# untitled.net
KiCad netlist of a schematic drawn in EAGLE
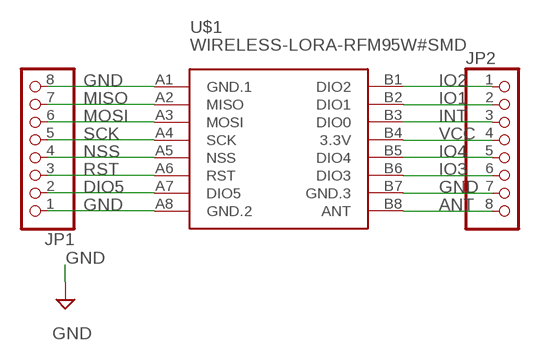
[diagram p0: schematic, sheet 1]

(export (version "E")
  (design (tool "Eeschema 10.0.6"))
  (components
    (comp (ref "JP1")
      (value "PINHD-1X8")
      (footprint "eagle-import:1X08")
      (libsource (lib "eagle-import") (part "PINHD-1X8"))
    )
    (comp (ref "JP2")
      (value "PINHD-1X8")
      (footprint "eagle-import:1X08")
      (libsource (lib "eagle-import") (part "PINHD-1X8"))
    )
    (comp (ref "U$1")
      (value "WIRELESS-LORA-RFM95W#SMD")
      (footprint "eagle-import:WIRELESS-LORA-RFM95W#SMD")
      (libsource (lib "eagle-import") (part "WIRELESS-LORA-RFM95W#SMD"))
    )
  )
  (nets
    (net (code "1") (name "/ANT") (class "Default")
      (node (ref "JP2") (pin "8") (pinfunction "8_8") (pintype "passive"))
      (node (ref "U$1") (pin "B8") (pinfunction "ANT_B8") (pintype "passive"))
    )
    (net (code "2") (name "/DIO5") (class "Default")
      (node (ref "JP1") (pin "2") (pinfunction "2_2") (pintype "passive"))
      (node (ref "U$1") (pin "A7") (pinfunction "DIO5_A7") (pintype "bidirectional"))
    )
    (net (code "3") (name "/INT") (class "Default")
      (node (ref "JP2") (pin "3") (pinfunction "3_3") (pintype "passive"))
      (node (ref "U$1") (pin "B3") (pinfunction "DIO0_B3") (pintype "bidirectional"))
    )
    (net (code "4") (name "/IO1") (class "Default")
      (node (ref "JP2") (pin "2") (pinfunction "2_2") (pintype "passive"))
      (node (ref "U$1") (pin "B2") (pinfunction "DIO1_B2") (pintype "bidirectional"))
    )
    (net (code "5") (name "/IO2") (class "Default")
      (node (ref "JP2") (pin "1") (pinfunction "1_1") (pintype "passive"))
      (node (ref "U$1") (pin "B1") (pinfunction "DIO2_B1") (pintype "bidirectional"))
    )
    (net (code "6") (name "/IO3") (class "Default")
      (node (ref "JP2") (pin "6") (pinfunction "6_6") (pintype "passive"))
      (node (ref "U$1") (pin "B6") (pinfunction "DIO3_B6") (pintype "bidirectional"))
    )
    (net (code "7") (name "/IO4") (class "Default")
      (node (ref "JP2") (pin "5") (pinfunction "5_5") (pintype "passive"))
      (node (ref "U$1") (pin "B5") (pinfunction "DIO4_B5") (pintype "bidirectional"))
    )
    (net (code "8") (name "/MISO") (class "Default")
      (node (ref "JP1") (pin "7") (pinfunction "7_7") (pintype "passive"))
      (node (ref "U$1") (pin "A2") (pinfunction "MISO_A2") (pintype "bidirectional"))
    )
    (net (code "9") (name "/MOSI") (class "Default")
      (node (ref "JP1") (pin "6") (pinfunction "6_6") (pintype "passive"))
      (node (ref "U$1") (pin "A3") (pinfunction "MOSI_A3") (pintype "bidirectional"))
    )
    (net (code "10") (name "/NSS") (class "Default")
      (node (ref "JP1") (pin "4") (pinfunction "4_4") (pintype "passive"))
      (node (ref "U$1") (pin "A5") (pinfunction "NSS_A5") (pintype "bidirectional"))
    )
    (net (code "11") (name "/RST") (class "Default")
      (node (ref "JP1") (pin "3") (pinfunction "3_3") (pintype "passive"))
      (node (ref "U$1") (pin "A6") (pinfunction "RST_A6") (pintype "bidirectional"))
    )
    (net (code "12") (name "/SCK") (class "Default")
      (node (ref "JP1") (pin "5") (pinfunction "5_5") (pintype "passive"))
      (node (ref "U$1") (pin "A4") (pinfunction "SCK_A4") (pintype "bidirectional"))
    )
    (net (code "13") (name "/VCC") (class "Default")
      (node (ref "JP2") (pin "4") (pinfunction "4_4") (pintype "passive"))
      (node (ref "U$1") (pin "B4") (pinfunction "3.3V_B4") (pintype "power_in"))
    )
    (net (code "14") (name "GND") (class "Default")
      (node (ref "JP1") (pin "1") (pinfunction "1_1") (pintype "passive"))
      (node (ref "JP1") (pin "8") (pinfunction "8_8") (pintype "passive"))
      (node (ref "JP2") (pin "7") (pinfunction "7_7") (pintype "passive"))
      (node (ref "U$1") (pin "A1") (pinfunction "GND.1_A1") (pintype "power_in"))
      (node (ref "U$1") (pin "A8") (pinfunction "GND.2_A8") (pintype "power_in"))
      (node (ref "U$1") (pin "B7") (pinfunction "GND.3_B7") (pintype "power_in"))
    )
  )
)
